# Apo_Board_2017_large.net
KiCad netlist of a schematic drawn in EAGLE
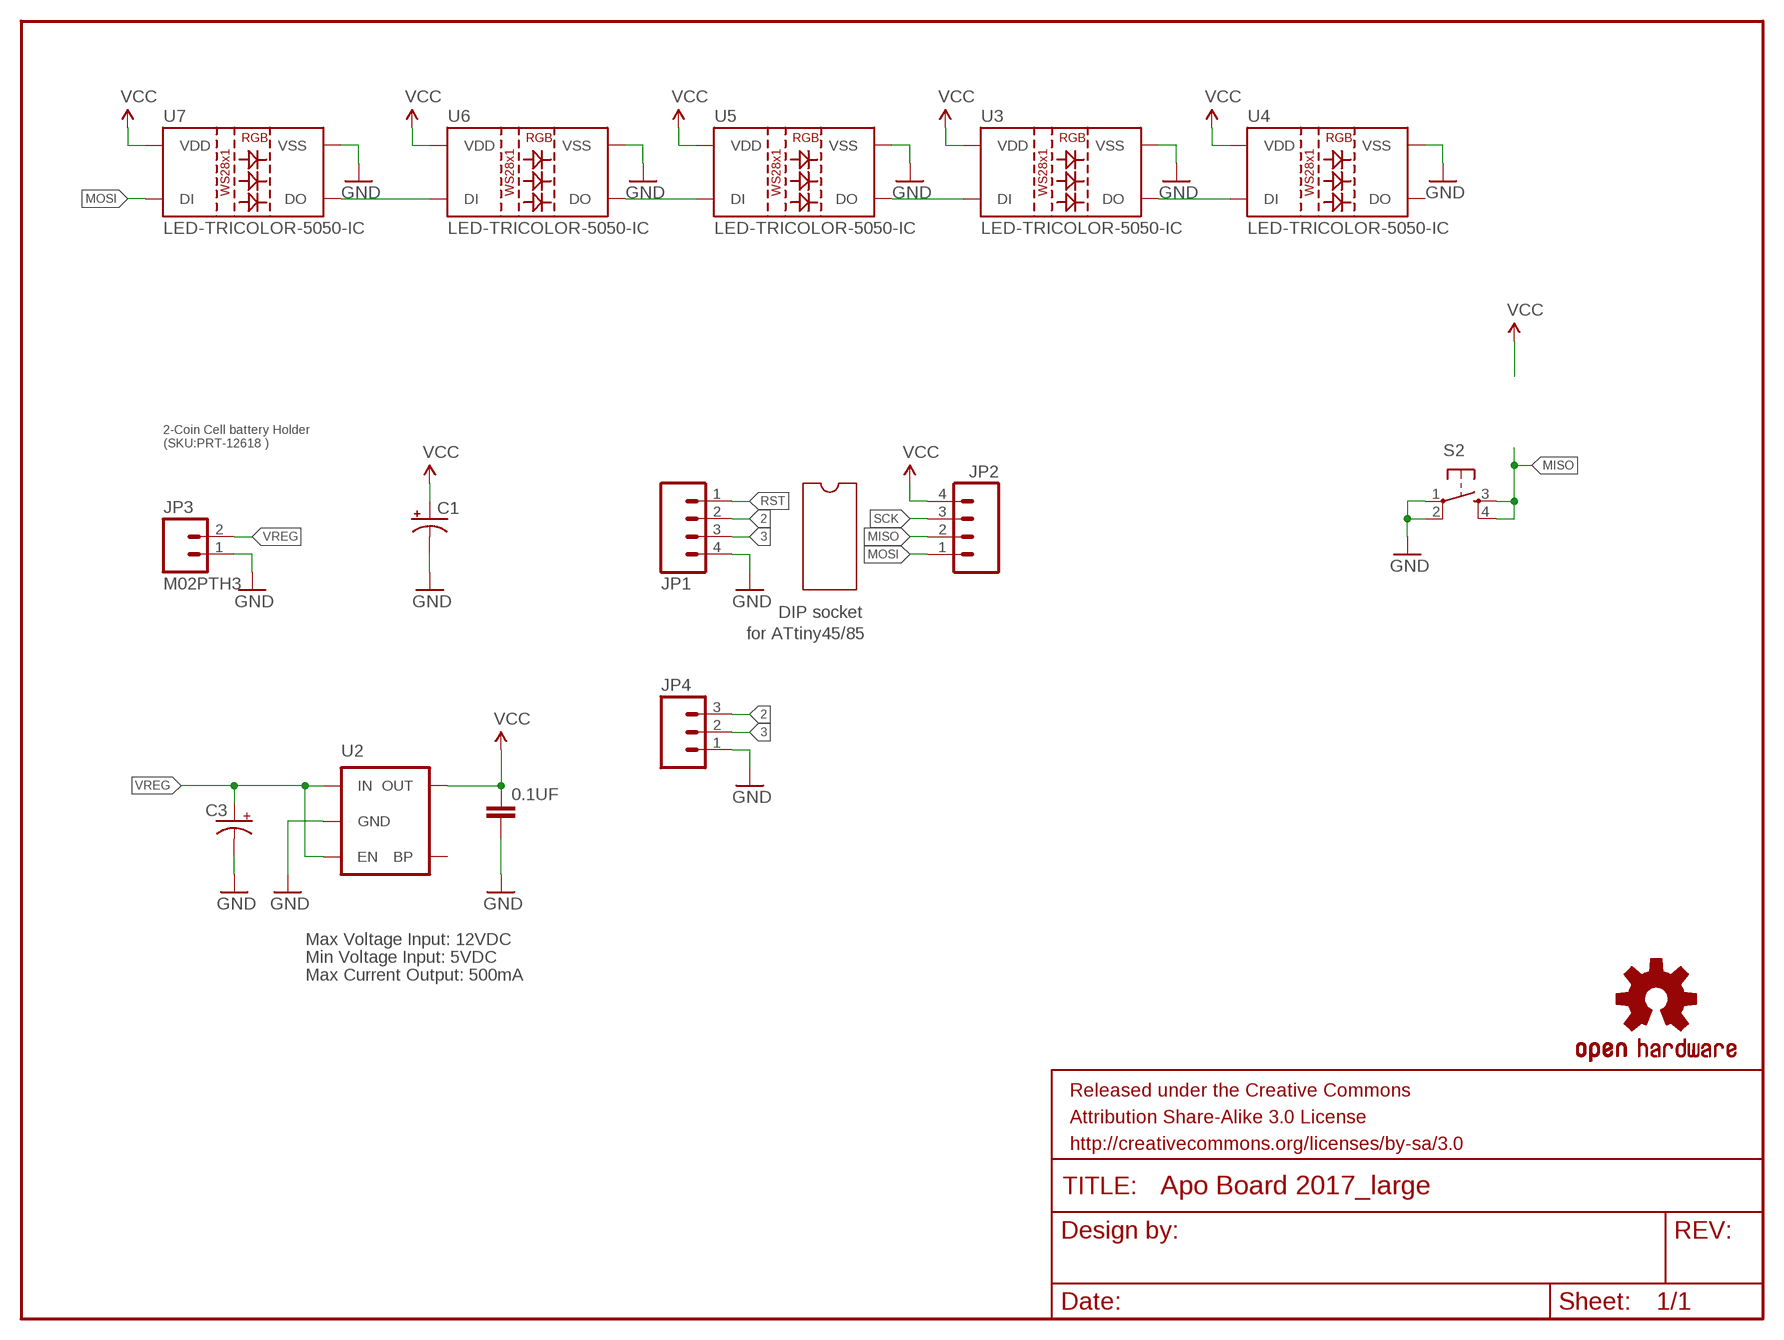
[diagram p0: schematic, sheet 1]

(export (version "E")
  (design (tool "Eeschema 10.0.6"))
  (components
    (comp (ref "0.1UF")
      (value "CAPKIT")
      (footprint "eagle-import:CAP-PTH-SMALL-KIT")
      (libsource (lib "eagle-import") (part "CAPKIT"))
    )
    (comp (ref "C1")
      (value "CAP_POLPTH2")
      (footprint "eagle-import:CPOL-RADIAL-10UF-25V")
      (libsource (lib "eagle-import") (part "CAP_POLPTH2"))
    )
    (comp (ref "C3")
      (value "CAP_POLPTH2")
      (footprint "eagle-import:CPOL-RADIAL-10UF-25V")
      (libsource (lib "eagle-import") (part "CAP_POLPTH2"))
    )
    (comp (ref "FRAME1")
      (value "FRAME-LETTER")
      (footprint "eagle-import:CREATIVE_COMMONS")
      (libsource (lib "eagle-import") (part "FRAME-LETTER"))
    )
    (comp (ref "JP1")
      (value "M04PTH")
      (footprint "eagle-import:1X04")
      (libsource (lib "eagle-import") (part "M04PTH"))
    )
    (comp (ref "JP2")
      (value "M04PTH")
      (footprint "eagle-import:1X04")
      (libsource (lib "eagle-import") (part "M04PTH"))
    )
    (comp (ref "JP3")
      (value "M02PTH3")
      (footprint "eagle-import:1X02_LONGPADS")
      (libsource (lib "eagle-import") (part "M02PTH3"))
    )
    (comp (ref "JP4")
      (value "M031X03_NO_SILK")
      (footprint "eagle-import:1X03_NO_SILK")
      (libsource (lib "eagle-import") (part "M031X03_NO_SILK"))
    )
    (comp (ref "LOGO1")
      (value "OSHW-LOGOS")
      (footprint "eagle-import:OSHW-LOGO-S")
      (libsource (lib "eagle-import") (part "OSHW-LOGOS"))
    )
    (comp (ref "S2")
      (value "TAC_SWITCHPTH")
      (footprint "eagle-import:TACTILE-PTH")
      (libsource (lib "eagle-import") (part "TAC_SWITCHPTH"))
    )
    (comp (ref "U2")
      (value "MIC52055V")
      (footprint "eagle-import:SOT23-5")
      (libsource (lib "eagle-import") (part "MIC52055V"))
    )
    (comp (ref "U3")
      (value "LED-TRICOLOR-5050-IC")
      (footprint "eagle-import:LED-RGB-THRU")
      (libsource (lib "eagle-import") (part "LED-TRICOLOR-5050-IC"))
    )
    (comp (ref "U4")
      (value "LED-TRICOLOR-5050-IC")
      (footprint "eagle-import:LED-RGB-THRU")
      (libsource (lib "eagle-import") (part "LED-TRICOLOR-5050-IC"))
    )
    (comp (ref "U5")
      (value "LED-TRICOLOR-5050-IC")
      (footprint "eagle-import:LED-RGB-THRU")
      (libsource (lib "eagle-import") (part "LED-TRICOLOR-5050-IC"))
    )
    (comp (ref "U6")
      (value "LED-TRICOLOR-5050-IC")
      (footprint "eagle-import:LED-RGB-THRU")
      (libsource (lib "eagle-import") (part "LED-TRICOLOR-5050-IC"))
    )
    (comp (ref "U7")
      (value "LED-TRICOLOR-5050-IC")
      (footprint "eagle-import:LED-RGB-THRU")
      (libsource (lib "eagle-import") (part "LED-TRICOLOR-5050-IC"))
    )
  )
  (nets
    (net (code "1") (name "2") (class "Default")
      (node (ref "JP1") (pin "2") (pinfunction "2_2") (pintype "passive"))
      (node (ref "JP4") (pin "3") (pinfunction "3_3") (pintype "passive"))
    )
    (net (code "2") (name "3") (class "Default")
      (node (ref "JP1") (pin "3") (pinfunction "3_3") (pintype "passive"))
      (node (ref "JP4") (pin "2") (pinfunction "2_2") (pintype "passive"))
    )
    (net (code "3") (name "GND") (class "Default")
      (node (ref "0.1UF") (pin "2") (pinfunction "2_2") (pintype "passive"))
      (node (ref "C1") (pin "2") (pinfunction "-_2") (pintype "passive"))
      (node (ref "C3") (pin "2") (pinfunction "-_2") (pintype "passive"))
      (node (ref "JP1") (pin "4") (pinfunction "4_4") (pintype "passive"))
      (node (ref "JP3") (pin "1") (pinfunction "1_1") (pintype "passive"))
      (node (ref "JP4") (pin "1") (pinfunction "1_1") (pintype "passive"))
      (node (ref "S2") (pin "1") (pinfunction "1_1") (pintype "passive"))
      (node (ref "S2") (pin "2") (pinfunction "2_2") (pintype "passive"))
      (node (ref "U2") (pin "2") (pinfunction "GND_2") (pintype "input"))
      (node (ref "U3") (pin "3") (pinfunction "VSS_3") (pintype "bidirectional"))
      (node (ref "U4") (pin "3") (pinfunction "VSS_3") (pintype "bidirectional"))
      (node (ref "U5") (pin "3") (pinfunction "VSS_3") (pintype "bidirectional"))
      (node (ref "U6") (pin "3") (pinfunction "VSS_3") (pintype "bidirectional"))
      (node (ref "U7") (pin "3") (pinfunction "VSS_3") (pintype "bidirectional"))
    )
    (net (code "4") (name "MISO") (class "Default")
      (node (ref "JP2") (pin "2") (pinfunction "2_2") (pintype "passive"))
      (node (ref "S2") (pin "3") (pinfunction "3_3") (pintype "passive"))
      (node (ref "S2") (pin "4") (pinfunction "4_4") (pintype "passive"))
    )
    (net (code "5") (name "MOSI") (class "Default")
      (node (ref "JP2") (pin "1") (pinfunction "1_1") (pintype "passive"))
      (node (ref "U7") (pin "1") (pinfunction "DI_1") (pintype "bidirectional"))
    )
    (net (code "6") (name "Net-(U3-DI)") (class "Default")
      (node (ref "U3") (pin "1") (pinfunction "DI_1") (pintype "bidirectional"))
      (node (ref "U5") (pin "4") (pinfunction "DO_4") (pintype "bidirectional"))
    )
    (net (code "7") (name "Net-(U3-DO)") (class "Default")
      (node (ref "U3") (pin "4") (pinfunction "DO_4") (pintype "bidirectional"))
      (node (ref "U4") (pin "1") (pinfunction "DI_1") (pintype "bidirectional"))
    )
    (net (code "8") (name "Net-(U5-DI)") (class "Default")
      (node (ref "U5") (pin "1") (pinfunction "DI_1") (pintype "bidirectional"))
      (node (ref "U6") (pin "4") (pinfunction "DO_4") (pintype "bidirectional"))
    )
    (net (code "9") (name "Net-(U6-DI)") (class "Default")
      (node (ref "U6") (pin "1") (pinfunction "DI_1") (pintype "bidirectional"))
      (node (ref "U7") (pin "4") (pinfunction "DO_4") (pintype "bidirectional"))
    )
    (net (code "10") (name "RST") (class "Default")
      (node (ref "JP1") (pin "1") (pinfunction "1_1") (pintype "passive"))
    )
    (net (code "11") (name "SCK") (class "Default")
      (node (ref "JP2") (pin "3") (pinfunction "3_3") (pintype "passive"))
    )
    (net (code "12") (name "VCC") (class "Default")
      (node (ref "0.1UF") (pin "1") (pinfunction "1_1") (pintype "passive"))
      (node (ref "C1") (pin "1") (pinfunction "+_1") (pintype "passive"))
      (node (ref "JP2") (pin "4") (pinfunction "4_4") (pintype "passive"))
      (node (ref "U2") (pin "5") (pinfunction "OUT_5") (pintype "passive"))
      (node (ref "U3") (pin "2") (pinfunction "VDD_2") (pintype "bidirectional"))
      (node (ref "U4") (pin "2") (pinfunction "VDD_2") (pintype "bidirectional"))
      (node (ref "U5") (pin "2") (pinfunction "VDD_2") (pintype "bidirectional"))
      (node (ref "U6") (pin "2") (pinfunction "VDD_2") (pintype "bidirectional"))
      (node (ref "U7") (pin "2") (pinfunction "VDD_2") (pintype "bidirectional"))
    )
    (net (code "13") (name "VREG") (class "Default")
      (node (ref "C3") (pin "1") (pinfunction "+_1") (pintype "passive"))
      (node (ref "JP3") (pin "2") (pinfunction "2_2") (pintype "passive"))
      (node (ref "U2") (pin "1") (pinfunction "IN_1") (pintype "input"))
      (node (ref "U2") (pin "3") (pinfunction "EN_3") (pintype "input"))
    )
    (net (code "14") (name "unconnected-(U2-BP-Pad4)") (class "Default")
      (node (ref "U2") (pin "4") (pinfunction "BP_4") (pintype "input"))
    )
    (net (code "15") (name "unconnected-(U4-DO-Pad4)") (class "Default")
      (node (ref "U4") (pin "4") (pinfunction "DO_4") (pintype "bidirectional"))
    )
  )
)
